# 2_PWR.net
KiCad netlist of a schematic drawn in Altium Designer
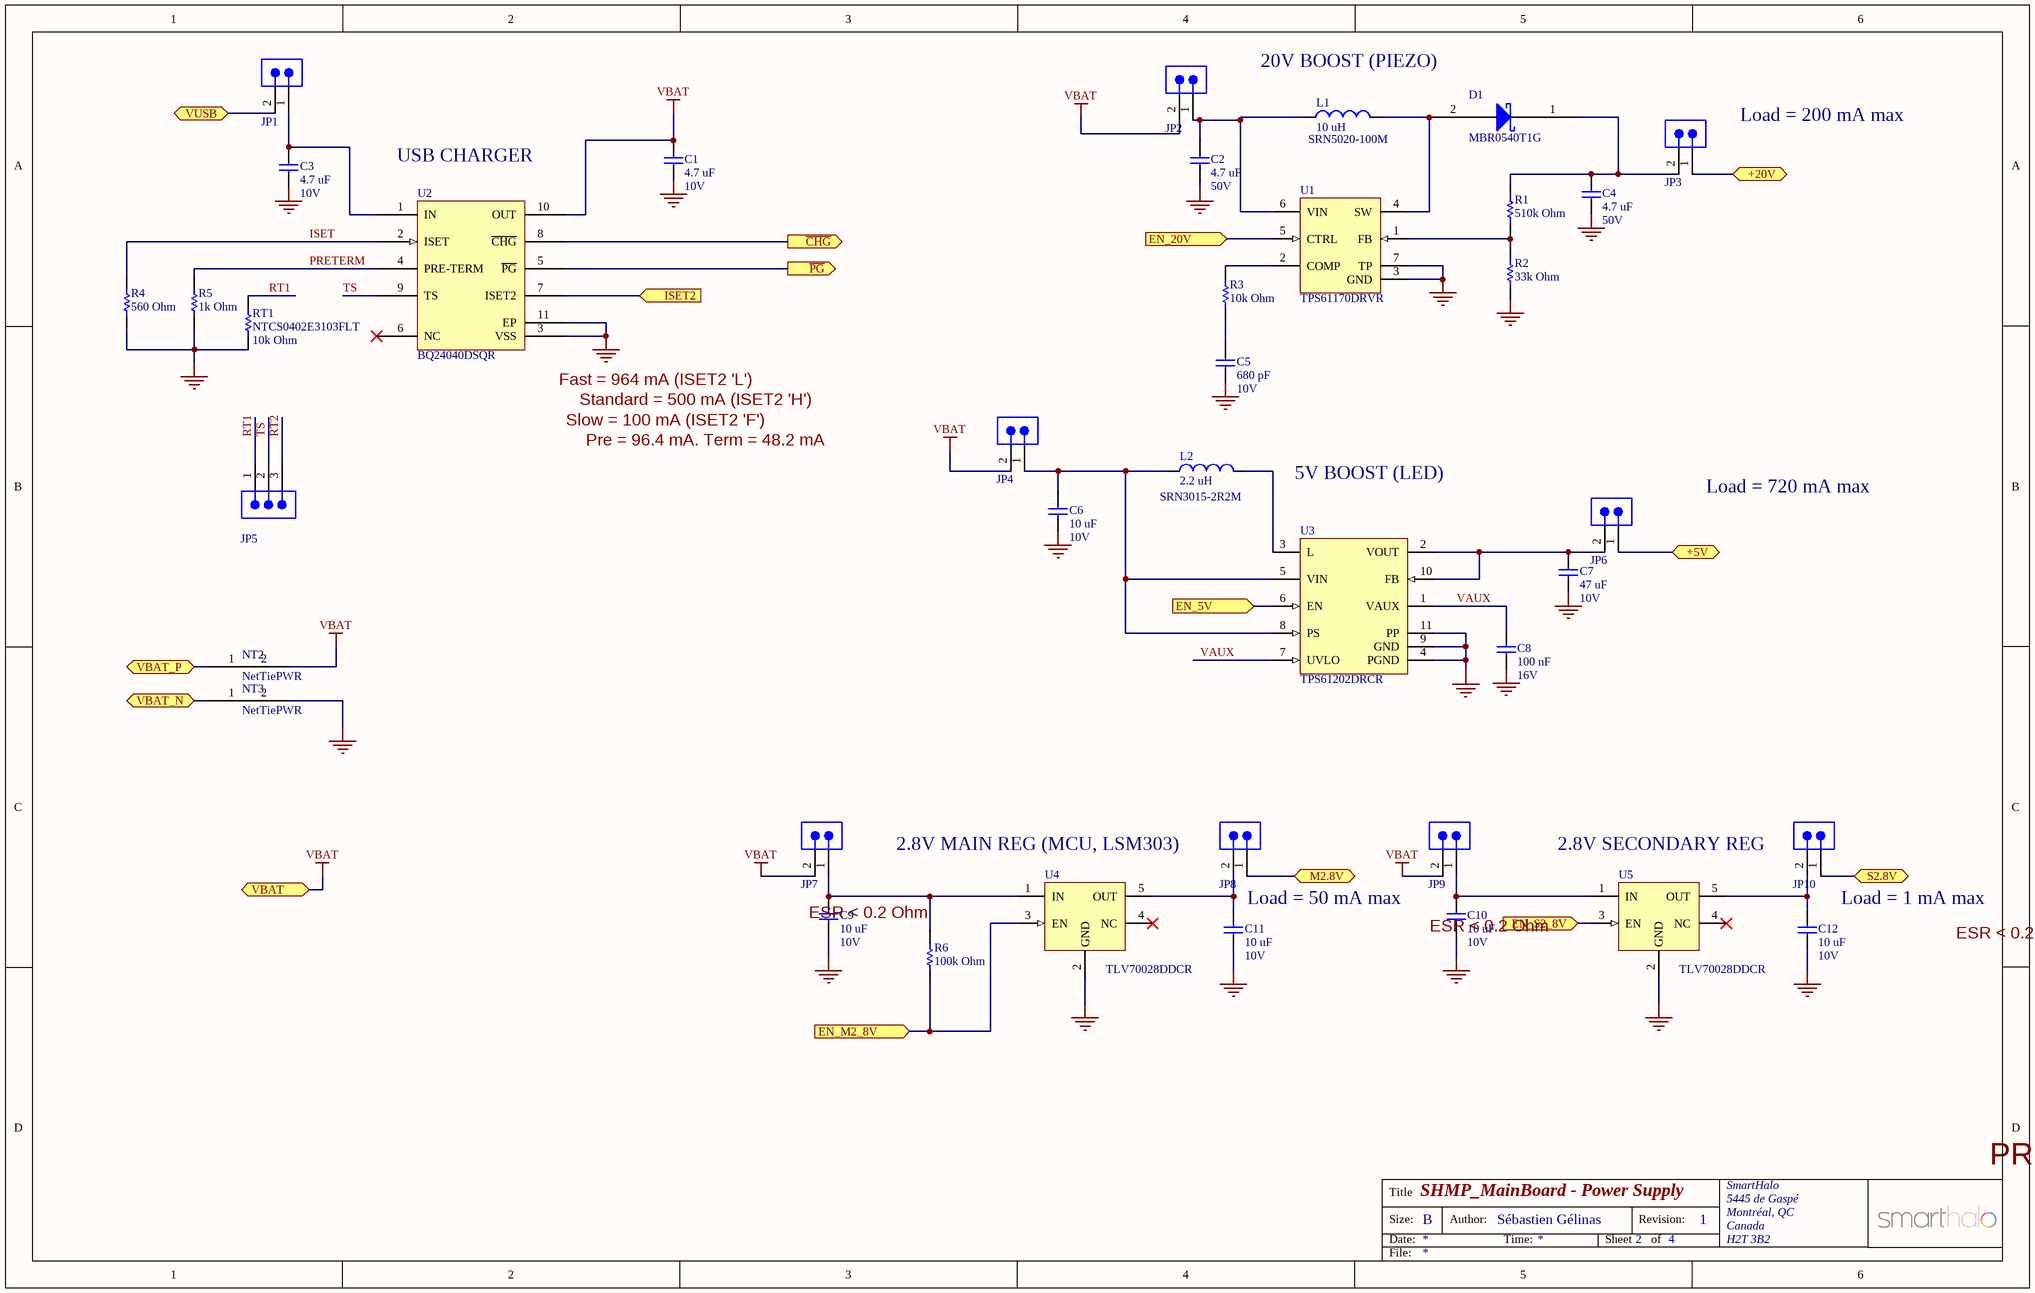
[diagram p0: 2_PWR.SchDoc]

(export (version "E")
  (design (tool "Eeschema 10.0.6"))
  (components
    (comp (ref "C1")
      (value "4.7 uF")
      (footprint "Varitron_CAP0603")
      (description "4.7 uF 10V X7R 10% 0603 (1608 Metric)  SMD")
      (fields (field (name "TOLERANCE") "10%") (field (name "VOLTAGE RATING") "10V"))
      (libsource (lib "SmartHalo") (part "Varitron_CAP0603"))
    )
    (comp (ref "C2")
      (value "4.7 uF")
      (footprint "Varitron_CAP0805")
      (description "4.7 uF 50V X5R 10% 0805 (2012 Metric)  SMD")
      (fields (field (name "TOLERANCE") "10%") (field (name "VOLTAGE RATING") "50V"))
      (libsource (lib "SmartHalo") (part "Varitron_CAP0805"))
    )
    (comp (ref "C3")
      (value "4.7 uF")
      (footprint "Varitron_CAP0603")
      (description "4.7 uF 10V X7R 10% 0603 (1608 Metric)  SMD")
      (fields (field (name "TOLERANCE") "10%") (field (name "VOLTAGE RATING") "10V"))
      (libsource (lib "SmartHalo") (part "Varitron_CAP0603"))
    )
    (comp (ref "C4")
      (value "4.7 uF")
      (footprint "Varitron_CAP0805")
      (description "4.7 uF 50V X5R 10% 0805 (2012 Metric)  SMD")
      (fields (field (name "TOLERANCE") "10%") (field (name "VOLTAGE RATING") "50V"))
      (libsource (lib "SmartHalo") (part "Varitron_CAP0805"))
    )
    (comp (ref "C5")
      (value "680 pF")
      (footprint "Varitron_CAP0402")
      (description "680 pF 10V X7R 10% 0402 (1005 Metric)  SMD")
      (fields (field (name "TOLERANCE") "10%") (field (name "VOLTAGE RATING") "10V"))
      (libsource (lib "SmartHalo") (part "Varitron_CAP0402"))
    )
    (comp (ref "C6")
      (value "10 uF")
      (footprint "Varitron_CAP0805")
      (description "10 uF 10V X7R 10% 0805 (2012 Metric)  SMD")
      (fields (field (name "TOLERANCE") "10%") (field (name "VOLTAGE RATING") "10V"))
      (libsource (lib "SmartHalo") (part "Varitron_CAP0805"))
    )
    (comp (ref "C7")
      (value "47 uF")
      (footprint "Varitron_CAP1206")
      (description "47 uF 10V X5R 10% 1206 (3216 Metric)  SMD")
      (fields (field (name "TOLERANCE") "10%") (field (name "VOLTAGE RATING") "10V"))
      (libsource (lib "SmartHalo") (part "Varitron_CAP1206"))
    )
    (comp (ref "C8")
      (value "100 nF")
      (footprint "Varitron_CAP0402")
      (description "100 nF 16V X7R 10% 0402 (1005 Metric)  SMD")
      (fields (field (name "TOLERANCE") "10%") (field (name "VOLTAGE RATING") "16V"))
      (libsource (lib "SmartHalo") (part "Varitron_CAP0402"))
    )
    (comp (ref "C9")
      (value "10 uF")
      (footprint "Varitron_CAP0805")
      (description "10 uF 10V X7R 10% 0805 (2012 Metric)  SMD")
      (fields (field (name "TOLERANCE") "10%") (field (name "VOLTAGE RATING") "10V"))
      (libsource (lib "SmartHalo") (part "Varitron_CAP0805"))
    )
    (comp (ref "C10")
      (value "10 uF")
      (footprint "Varitron_CAP0805")
      (description "10 uF 10V X7R 10% 0805 (2012 Metric)  SMD")
      (fields (field (name "TOLERANCE") "10%") (field (name "VOLTAGE RATING") "10V"))
      (libsource (lib "SmartHalo") (part "Varitron_CAP0805"))
    )
    (comp (ref "C11")
      (value "10 uF")
      (footprint "Varitron_CAP0805")
      (description "10 uF 10V X7R 10% 0805 (2012 Metric)  SMD")
      (fields (field (name "TOLERANCE") "10%") (field (name "VOLTAGE RATING") "10V"))
      (libsource (lib "SmartHalo") (part "Varitron_CAP0805"))
    )
    (comp (ref "C12")
      (value "10 uF")
      (footprint "Varitron_CAP0805")
      (description "10 uF 10V X7R 10% 0805 (2012 Metric)  SMD")
      (fields (field (name "TOLERANCE") "10%") (field (name "VOLTAGE RATING") "10V"))
      (libsource (lib "SmartHalo") (part "Varitron_CAP0805"))
    )
    (comp (ref "D1")
      (value "MBR0540T1G")
      (footprint "ONSC-SOD-123-2-425-04_V")
      (description "Schottky Power Rectifier, 2-Pin SOD-123, Pb-Free, Tape and Reel")
      (fields (field (name "MANUFACTURER") "ON Semiconductor"))
      (libsource (lib "SmartHalo") (part "MBR0540T1G"))
    )
    (comp (ref "JP1")
      (value "JMP_2PINS_100MILS")
      (footprint "HDR_2X1_100MILS")
      (description "Jumper, 100 mils, 2 pins")
      (libsource (lib "SmartHalo") (part "JMP_2PINS_100MILS"))
    )
    (comp (ref "JP2")
      (value "JMP_2PINS_100MILS")
      (footprint "HDR_2X1_100MILS")
      (description "Jumper, 100 mils, 2 pins")
      (libsource (lib "SmartHalo") (part "JMP_2PINS_100MILS"))
    )
    (comp (ref "JP3")
      (value "JMP_2PINS_100MILS")
      (footprint "HDR_2X1_100MILS")
      (description "Jumper, 100 mils, 2 pins")
      (libsource (lib "SmartHalo") (part "JMP_2PINS_100MILS"))
    )
    (comp (ref "JP4")
      (value "JMP_2PINS_100MILS")
      (footprint "HDR_2X1_100MILS")
      (description "Jumper, 100 mils, 2 pins")
      (libsource (lib "SmartHalo") (part "JMP_2PINS_100MILS"))
    )
    (comp (ref "JP5")
      (value "JMP_3PINS_100MILS")
      (footprint "HDR_1X3_100MILS")
      (description "Jumper, 100 mils, 3 pins")
      (libsource (lib "SmartHalo") (part "JMP_3PINS_100MILS"))
    )
    (comp (ref "JP6")
      (value "JMP_2PINS_100MILS")
      (footprint "HDR_2X1_100MILS")
      (description "Jumper, 100 mils, 2 pins")
      (libsource (lib "SmartHalo") (part "JMP_2PINS_100MILS"))
    )
    (comp (ref "JP7")
      (value "JMP_2PINS_100MILS")
      (footprint "HDR_2X1_100MILS")
      (description "Jumper, 100 mils, 2 pins")
      (libsource (lib "SmartHalo") (part "JMP_2PINS_100MILS"))
    )
    (comp (ref "JP8")
      (value "JMP_2PINS_100MILS")
      (footprint "HDR_2X1_100MILS")
      (description "Jumper, 100 mils, 2 pins")
      (libsource (lib "SmartHalo") (part "JMP_2PINS_100MILS"))
    )
    (comp (ref "JP9")
      (value "JMP_2PINS_100MILS")
      (footprint "HDR_2X1_100MILS")
      (description "Jumper, 100 mils, 2 pins")
      (libsource (lib "SmartHalo") (part "JMP_2PINS_100MILS"))
    )
    (comp (ref "JP10")
      (value "JMP_2PINS_100MILS")
      (footprint "HDR_2X1_100MILS")
      (description "Jumper, 100 mils, 2 pins")
      (libsource (lib "SmartHalo") (part "JMP_2PINS_100MILS"))
    )
    (comp (ref "L1")
      (value "10 uH")
      (footprint "SRN5020-100M")
      (description "Inductor, 10 uH, 20%, 144 mOhm DCR, 1.3A")
      (fields
        (field (name "MANUFACTURER") "Bourns")
        (field (name "MANUFACTURER PART NUMBER") "SRN5020-100M")
        (field (name "PART NUMBER") "SRN5020-100M")
      )
      (libsource (lib "SmartHalo") (part "SRN5020-100M"))
    )
    (comp (ref "L2")
      (value "2.2 uH")
      (footprint "SRN3015-2R2M")
      (description "Inductor, 2.2 uH, 20%, 72 mOhm DCR, 1.65A")
      (fields
        (field (name "MANUFACTURER") "Bourns")
        (field (name "MANUFACTURER PART NUMBER") "SRN3015-2R2M")
        (field (name "PART NUMBER") "SRN3015-2R2M")
      )
      (libsource (lib "SmartHalo") (part "SRN3015-2R2M"))
    )
    (comp (ref "NT2")
      (value "NetTiePWR")
      (footprint "NetTiePWR")
      (libsource (lib "SmartHalo") (part "NetTiePWR"))
    )
    (comp (ref "NT3")
      (value "NetTiePWR")
      (footprint "NetTiePWR")
      (libsource (lib "SmartHalo") (part "NetTiePWR"))
    )
    (comp (ref "R1")
      (value "510k Ohm")
      (footprint "Varitron_RES0402")
      (description "510k 0.063W 5%  0402 (1005 Metric)  SMD")
      (fields (field (name "TOLERANCE") "5%") (field (name "POWER") "0.063W"))
      (libsource (lib "SmartHalo") (part "Varitron_RES0402"))
    )
    (comp (ref "R2")
      (value "33k Ohm")
      (footprint "Varitron_RES0402")
      (description "33k 0.063W 5%  0402 (1005 Metric)  SMD")
      (fields (field (name "TOLERANCE") "5%") (field (name "POWER") "0.063W"))
      (libsource (lib "SmartHalo") (part "Varitron_RES0402"))
    )
    (comp (ref "R3")
      (value "10k Ohm")
      (footprint "Varitron_RES0402")
      (description "10k 0.063W 5%  0402 (1005 Metric)  SMD")
      (fields (field (name "TOLERANCE") "5%") (field (name "POWER") "0.063W"))
      (libsource (lib "SmartHalo") (part "Varitron_RES0402"))
    )
    (comp (ref "R4")
      (value "560 Ohm")
      (footprint "Varitron_RES0402")
      (description "560R 0.063W 5%  0402 (1005 Metric)  SMD")
      (fields (field (name "TOLERANCE") "5%") (field (name "POWER") "0.063W"))
      (libsource (lib "SmartHalo") (part "Varitron_RES0402"))
    )
    (comp (ref "R5")
      (value "1k Ohm")
      (footprint "Varitron_RES0402")
      (description "1k 0.063W 5%  0402 (1005 Metric)  SMD")
      (fields (field (name "TOLERANCE") "5%") (field (name "POWER") "0.063W"))
      (libsource (lib "SmartHalo") (part "Varitron_RES0402"))
    )
    (comp (ref "R6")
      (value "100k Ohm")
      (footprint "Varitron_RES0402")
      (description "100k 0.063W 5%  0402 (1005 Metric)  SMD")
      (fields (field (name "TOLERANCE") "5%") (field (name "POWER") "0.063W"))
      (libsource (lib "SmartHalo") (part "Varitron_RES0402"))
    )
    (comp (ref "RT1")
      (value "NTCS0402E3103FLT")
      (footprint "Varitron_RES0402")
      (description "Thermistor NTC 0402, R0 10k, 1%, B 3490, SMD")
      (fields
        (field (name "TOLERANCE") "1%")
        (field (name "MANUFACTURER") "Vishay")
        (field (name "ALTIUM_VALUE") "10k Ohm")
      )
      (libsource (lib "SmartHalo") (part "NTCS0402E3103FLT"))
    )
    (comp (ref "U1")
      (value "TPS61170DRVR")
      (footprint "DRV6-1600X1000TP")
      (fields (field (name "MANUFACTURER") "Texas Instruments"))
      (libsource (lib "SmartHalo") (part "TPS61170DRVR"))
    )
    (comp (ref "U2")
      (value "BQ24040DSQR")
      (footprint "DSQ10-1500X900TP")
      (fields (field (name "MANUFACTURER") "Texas Instruments"))
      (libsource (lib "SmartHalo") (part "BQ24040DSQR"))
    )
    (comp (ref "U3")
      (value "TPS61202DRCR")
      (footprint "DRC10-2400X1650TP")
      (fields (field (name "MANUFACTURER") "Texas Instruments"))
      (libsource (lib "SmartHalo") (part "TPS61202DRCR"))
    )
    (comp (ref "U4")
      (value "TLV70028DDCR")
      (footprint "SOT23-5_N")
      (description "200 mA Low Dropout Regulator, 2 - 5.5V Input, Fixed 2.8V Output")
      (fields (field (name "MANUFACTURER") "Texas Instruments"))
      (libsource (lib "SmartHalo") (part "TLV70028DDCR"))
    )
    (comp (ref "U5")
      (value "TLV70028DDCR")
      (footprint "SOT23-5_N")
      (description "200 mA Low Dropout Regulator, 2 - 5.5V Input, Fixed 2.8V Output")
      (fields (field (name "MANUFACTURER") "Texas Instruments"))
      (libsource (lib "SmartHalo") (part "TLV70028DDCR"))
    )
  )
  (nets
    (net (code "1") (name "/+5V") (class "Default")
      (node (ref "JP6") (pin "1") (pinfunction "1_1") (pintype "passive"))
    )
    (net (code "2") (name "/+20V") (class "Default")
      (node (ref "JP3") (pin "1") (pinfunction "1_1") (pintype "passive"))
    )
    (net (code "3") (name "/EN_5V") (class "Default")
      (node (ref "U3") (pin "6") (pinfunction "EN_6") (pintype "input"))
    )
    (net (code "4") (name "/EN_20V") (class "Default")
      (node (ref "U1") (pin "5") (pinfunction "CTRL_5") (pintype "input"))
    )
    (net (code "5") (name "/EN_M2_8V") (class "Default")
      (node (ref "R6") (pin "1") (pinfunction "1_1") (pintype "passive"))
      (node (ref "U4") (pin "3") (pinfunction "EN_3") (pintype "input"))
    )
    (net (code "6") (name "/EN_S2_8V") (class "Default")
      (node (ref "U5") (pin "3") (pinfunction "EN_3") (pintype "input"))
    )
    (net (code "7") (name "/ISET") (class "Default")
      (node (ref "R4") (pin "1") (pinfunction "1_1") (pintype "passive"))
      (node (ref "U2") (pin "2") (pinfunction "ISET_2") (pintype "input"))
    )
    (net (code "8") (name "/ISET2") (class "Default")
      (node (ref "U2") (pin "7") (pinfunction "ISET2_7") (pintype "passive"))
    )
    (net (code "9") (name "/M2.8V") (class "Default")
      (node (ref "JP8") (pin "1") (pinfunction "1_1") (pintype "passive"))
    )
    (net (code "10") (name "/PRETERM") (class "Default")
      (node (ref "R5") (pin "1") (pinfunction "1_1") (pintype "passive"))
      (node (ref "U2") (pin "4") (pinfunction "PRE-TERM_4") (pintype "passive"))
    )
    (net (code "11") (name "/RT1") (class "Default")
      (node (ref "JP5") (pin "1") (pinfunction "1_1") (pintype "passive"))
      (node (ref "RT1") (pin "2") (pinfunction "2_2") (pintype "passive"))
    )
    (net (code "12") (name "/RT2") (class "Default")
      (node (ref "JP5") (pin "3") (pinfunction "3_3") (pintype "passive"))
    )
    (net (code "13") (name "/S2.8V") (class "Default")
      (node (ref "JP10") (pin "1") (pinfunction "1_1") (pintype "passive"))
    )
    (net (code "14") (name "/TS") (class "Default")
      (node (ref "JP5") (pin "2") (pinfunction "2_2") (pintype "passive"))
      (node (ref "U2") (pin "9") (pinfunction "TS_9") (pintype "passive"))
    )
    (net (code "15") (name "/VAUX") (class "Default")
      (node (ref "C8") (pin "1") (pinfunction "1_1") (pintype "passive"))
      (node (ref "U3") (pin "1") (pinfunction "VAUX_1") (pintype "power_in"))
      (node (ref "U3") (pin "7") (pinfunction "UVLO_7") (pintype "input"))
    )
    (net (code "16") (name "/VBAT_N") (class "Default")
      (node (ref "NT3") (pin "1") (pinfunction "NET1_1") (pintype "passive"))
    )
    (net (code "17") (name "/VBAT_P") (class "Default")
      (node (ref "NT2") (pin "1") (pinfunction "NET1_1") (pintype "passive"))
    )
    (net (code "18") (name "/VUSB") (class "Default")
      (node (ref "JP1") (pin "2") (pinfunction "2_2") (pintype "passive"))
    )
    (net (code "19") (name "/~{CHG}") (class "Default")
      (node (ref "U2") (pin "8") (pinfunction "~{CHG}_8") (pintype "passive"))
    )
    (net (code "20") (name "/~{PG}") (class "Default")
      (node (ref "U2") (pin "5") (pinfunction "~{PG}_5") (pintype "passive"))
    )
    (net (code "21") (name "GND") (class "Default")
      (node (ref "C1") (pin "2") (pinfunction "2_2") (pintype "passive"))
      (node (ref "C10") (pin "2") (pinfunction "2_2") (pintype "passive"))
      (node (ref "C11") (pin "2") (pinfunction "2_2") (pintype "passive"))
      (node (ref "C12") (pin "2") (pinfunction "2_2") (pintype "passive"))
      (node (ref "C2") (pin "2") (pinfunction "2_2") (pintype "passive"))
      (node (ref "C3") (pin "2") (pinfunction "2_2") (pintype "passive"))
      (node (ref "C4") (pin "2") (pinfunction "2_2") (pintype "passive"))
      (node (ref "C5") (pin "2") (pinfunction "2_2") (pintype "passive"))
      (node (ref "C6") (pin "2") (pinfunction "2_2") (pintype "passive"))
      (node (ref "C7") (pin "2") (pinfunction "2_2") (pintype "passive"))
      (node (ref "C8") (pin "2") (pinfunction "2_2") (pintype "passive"))
      (node (ref "C9") (pin "2") (pinfunction "2_2") (pintype "passive"))
      (node (ref "NT3") (pin "2") (pinfunction "NET2_2") (pintype "passive"))
      (node (ref "R2") (pin "1") (pinfunction "1_1") (pintype "passive"))
      (node (ref "R4") (pin "2") (pinfunction "2_2") (pintype "passive"))
      (node (ref "R5") (pin "2") (pinfunction "2_2") (pintype "passive"))
      (node (ref "RT1") (pin "1") (pinfunction "1_1") (pintype "passive"))
      (node (ref "U1") (pin "3") (pinfunction "GND_3") (pintype "power_in"))
      (node (ref "U1") (pin "7") (pinfunction "TP_7") (pintype "power_in"))
      (node (ref "U2") (pin "11") (pinfunction "EP_11") (pintype "power_in"))
      (node (ref "U2") (pin "3") (pinfunction "VSS_3") (pintype "power_in"))
      (node (ref "U3") (pin "11") (pinfunction "PP_11") (pintype "power_in"))
      (node (ref "U3") (pin "4") (pinfunction "PGND_4") (pintype "power_in"))
      (node (ref "U3") (pin "9") (pinfunction "GND_9") (pintype "power_in"))
      (node (ref "U4") (pin "2") (pinfunction "GND_2") (pintype "power_in"))
      (node (ref "U5") (pin "2") (pinfunction "GND_2") (pintype "power_in"))
    )
    (net (code "22") (name "Net-(C5-Pad1)") (class "Default")
      (node (ref "C5") (pin "1") (pinfunction "1_1") (pintype "passive"))
      (node (ref "R3") (pin "2") (pinfunction "2_2") (pintype "passive"))
    )
    (net (code "23") (name "Net-(D1-Anode)") (class "Default")
      (node (ref "D1") (pin "2") (pinfunction "Anode_2") (pintype "passive"))
      (node (ref "L1") (pin "2") (pinfunction "2_2") (pintype "passive"))
      (node (ref "U1") (pin "4") (pinfunction "SW_4") (pintype "power_in"))
    )
    (net (code "24") (name "Net-(D1-Cathode)") (class "Default")
      (node (ref "C4") (pin "1") (pinfunction "1_1") (pintype "passive"))
      (node (ref "D1") (pin "1") (pinfunction "Cathode_1") (pintype "passive"))
      (node (ref "JP3") (pin "2") (pinfunction "2_2") (pintype "passive"))
      (node (ref "R1") (pin "2") (pinfunction "2_2") (pintype "passive"))
    )
    (net (code "25") (name "Net-(U1-COMP)") (class "Default")
      (node (ref "R3") (pin "1") (pinfunction "1_1") (pintype "passive"))
      (node (ref "U1") (pin "2") (pinfunction "COMP_2") (pintype "passive"))
    )
    (net (code "26") (name "Net-(U1-FB)") (class "Default")
      (node (ref "R1") (pin "1") (pinfunction "1_1") (pintype "passive"))
      (node (ref "R2") (pin "2") (pinfunction "2_2") (pintype "passive"))
      (node (ref "U1") (pin "1") (pinfunction "FB_1") (pintype "input"))
    )
    (net (code "27") (name "Net-(U1-VIN)") (class "Default")
      (node (ref "C2") (pin "1") (pinfunction "1_1") (pintype "passive"))
      (node (ref "JP2") (pin "1") (pinfunction "1_1") (pintype "passive"))
      (node (ref "L1") (pin "1") (pinfunction "1_1") (pintype "passive"))
      (node (ref "U1") (pin "6") (pinfunction "VIN_6") (pintype "power_in"))
    )
    (net (code "28") (name "Net-(U2-IN)") (class "Default")
      (node (ref "C3") (pin "1") (pinfunction "1_1") (pintype "passive"))
      (node (ref "JP1") (pin "1") (pinfunction "1_1") (pintype "passive"))
      (node (ref "U2") (pin "1") (pinfunction "IN_1") (pintype "power_in"))
    )
    (net (code "29") (name "Net-(U3-FB)") (class "Default")
      (node (ref "C7") (pin "1") (pinfunction "1_1") (pintype "passive"))
      (node (ref "JP6") (pin "2") (pinfunction "2_2") (pintype "passive"))
      (node (ref "U3") (pin "10") (pinfunction "FB_10") (pintype "input"))
      (node (ref "U3") (pin "2") (pinfunction "VOUT_2") (pintype "power_in"))
    )
    (net (code "30") (name "Net-(U3-L)") (class "Default")
      (node (ref "L2") (pin "2") (pinfunction "2_2") (pintype "passive"))
      (node (ref "U3") (pin "3") (pinfunction "L_3") (pintype "power_in"))
    )
    (net (code "31") (name "Net-(U3-PS)") (class "Default")
      (node (ref "C6") (pin "1") (pinfunction "1_1") (pintype "passive"))
      (node (ref "JP4") (pin "1") (pinfunction "1_1") (pintype "passive"))
      (node (ref "L2") (pin "1") (pinfunction "1_1") (pintype "passive"))
      (node (ref "U3") (pin "5") (pinfunction "VIN_5") (pintype "power_in"))
      (node (ref "U3") (pin "8") (pinfunction "PS_8") (pintype "input"))
    )
    (net (code "32") (name "Net-(U4-IN)") (class "Default")
      (node (ref "C9") (pin "1") (pinfunction "1_1") (pintype "passive"))
      (node (ref "JP7") (pin "1") (pinfunction "1_1") (pintype "passive"))
      (node (ref "R6") (pin "2") (pinfunction "2_2") (pintype "passive"))
      (node (ref "U4") (pin "1") (pinfunction "IN_1") (pintype "power_in"))
    )
    (net (code "33") (name "Net-(U4-OUT)") (class "Default")
      (node (ref "C11") (pin "1") (pinfunction "1_1") (pintype "passive"))
      (node (ref "JP8") (pin "2") (pinfunction "2_2") (pintype "passive"))
      (node (ref "U4") (pin "5") (pinfunction "OUT_5") (pintype "power_in"))
    )
    (net (code "34") (name "Net-(U5-IN)") (class "Default")
      (node (ref "C10") (pin "1") (pinfunction "1_1") (pintype "passive"))
      (node (ref "JP9") (pin "1") (pinfunction "1_1") (pintype "passive"))
      (node (ref "U5") (pin "1") (pinfunction "IN_1") (pintype "power_in"))
    )
    (net (code "35") (name "Net-(U5-OUT)") (class "Default")
      (node (ref "C12") (pin "1") (pinfunction "1_1") (pintype "passive"))
      (node (ref "JP10") (pin "2") (pinfunction "2_2") (pintype "passive"))
      (node (ref "U5") (pin "5") (pinfunction "OUT_5") (pintype "power_in"))
    )
    (net (code "36") (name "VBAT") (class "Default")
      (node (ref "C1") (pin "1") (pinfunction "1_1") (pintype "passive"))
      (node (ref "JP2") (pin "2") (pinfunction "2_2") (pintype "passive"))
      (node (ref "JP4") (pin "2") (pinfunction "2_2") (pintype "passive"))
      (node (ref "JP7") (pin "2") (pinfunction "2_2") (pintype "passive"))
      (node (ref "JP9") (pin "2") (pinfunction "2_2") (pintype "passive"))
      (node (ref "NT2") (pin "2") (pinfunction "NET2_2") (pintype "passive"))
      (node (ref "U2") (pin "10") (pinfunction "OUT_10") (pintype "power_in"))
    )
    (net (code "37") (name "unconnected-(U2-NC-Pad6)") (class "Default")
      (node (ref "U2") (pin "6") (pinfunction "NC_6") (pintype "passive+no_connect"))
    )
    (net (code "38") (name "unconnected-(U4-NC-Pad4)") (class "Default")
      (node (ref "U4") (pin "4") (pinfunction "NC_4") (pintype "passive+no_connect"))
    )
    (net (code "39") (name "unconnected-(U5-NC-Pad4)") (class "Default")
      (node (ref "U5") (pin "4") (pinfunction "NC_4") (pintype "passive+no_connect"))
    )
  )
)
